# USB2_Replication.net
KiCad netlist of a schematic drawn in Altium Designer
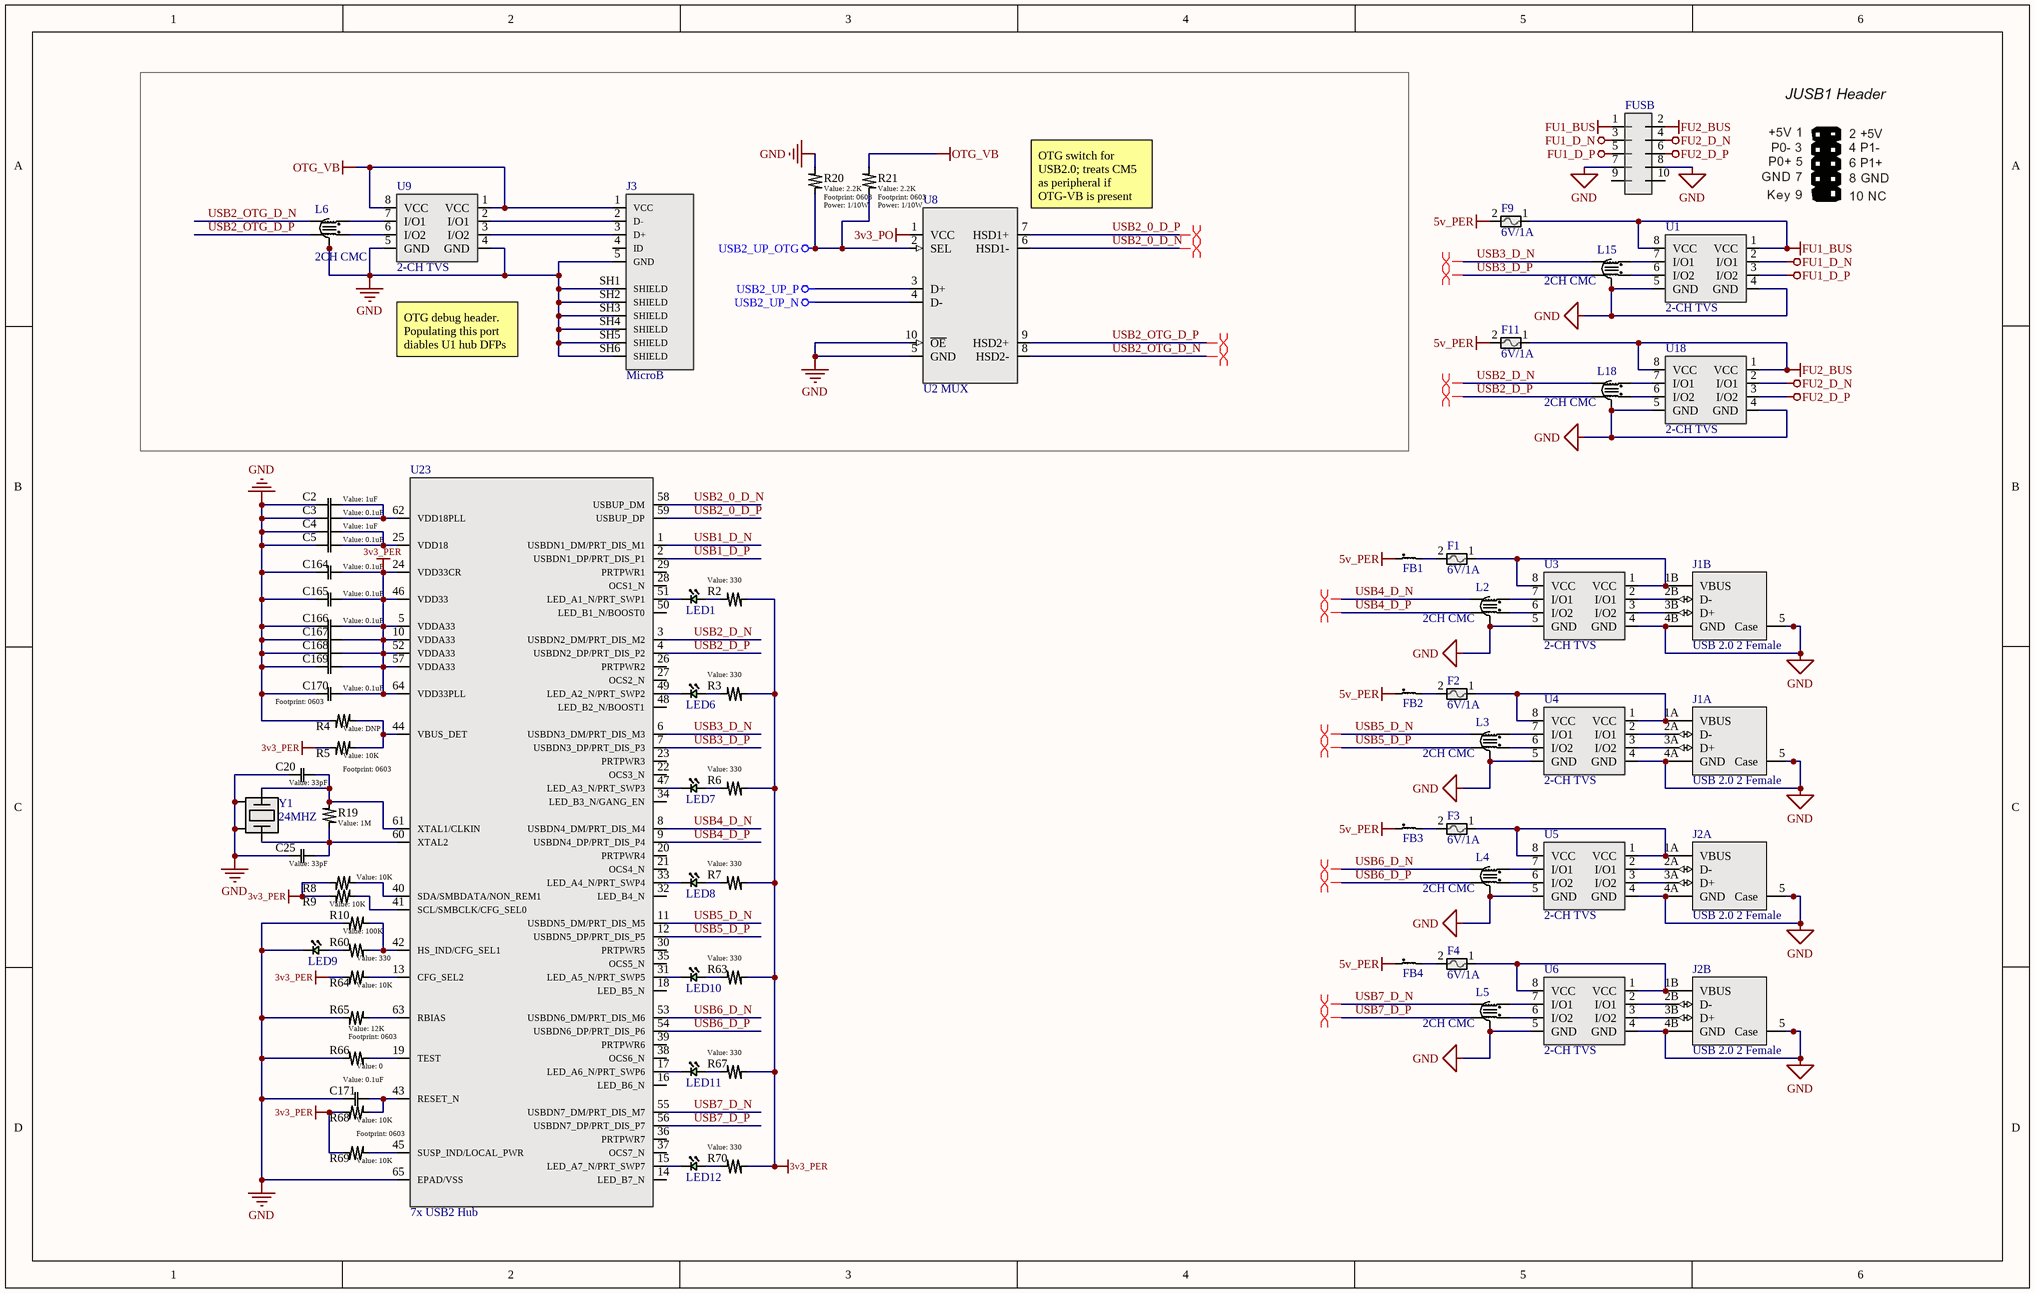
[diagram p0: USB2_Replication.SchDoc]

(export (version "E")
  (design (tool "Eeschema 10.0.6"))
  (components
    (comp (ref "C2")
      (value "1uF")
      (footprint "0603")
      (fields
        (field (name "VOLTAGE") "10V")
        (field (name "TOLERANCE") "10%")
        (field (name "Comment") "Generic Capacitor")
      )
      (libsource (lib "Capacitors") (part "Generic Capacitor"))
    )
    (comp (ref "C3")
      (value "0.1uF")
      (footprint "0603")
      (fields
        (field (name "VOLTAGE") "10V")
        (field (name "TOLERANCE") "10%")
        (field (name "Comment") "Generic Capacitor")
      )
      (libsource (lib "Capacitors") (part "Generic Capacitor"))
    )
    (comp (ref "C4")
      (value "1uF")
      (footprint "0603")
      (fields
        (field (name "VOLTAGE") "10V")
        (field (name "TOLERANCE") "10%")
        (field (name "Comment") "Generic Capacitor")
      )
      (libsource (lib "Capacitors") (part "Generic Capacitor"))
    )
    (comp (ref "C5")
      (value "0.1uF")
      (footprint "0603")
      (fields
        (field (name "VOLTAGE") "10V")
        (field (name "TOLERANCE") "10%")
        (field (name "Comment") "Generic Capacitor")
      )
      (libsource (lib "Capacitors") (part "Generic Capacitor"))
    )
    (comp (ref "C20")
      (value "33pF")
      (footprint "0603")
      (fields
        (field (name "VOLTAGE") "10V")
        (field (name "TOLERANCE") "10%")
        (field (name "Comment") "Generic Capacitor")
      )
      (libsource (lib "Capacitors") (part "Generic Capacitor"))
    )
    (comp (ref "C25")
      (value "33pF")
      (footprint "0603")
      (fields
        (field (name "VOLTAGE") "10V")
        (field (name "TOLERANCE") "10%")
        (field (name "Comment") "Generic Capacitor")
      )
      (libsource (lib "Capacitors") (part "Generic Capacitor"))
    )
    (comp (ref "C164")
      (value "0.1uF")
      (footprint "0603")
      (fields
        (field (name "VOLTAGE") "10V")
        (field (name "TOLERANCE") "10%")
        (field (name "Comment") "Generic Capacitor")
      )
      (libsource (lib "Capacitors") (part "Generic Capacitor"))
    )
    (comp (ref "C165")
      (value "0.1uF")
      (footprint "0603")
      (fields
        (field (name "VOLTAGE") "10V")
        (field (name "TOLERANCE") "10%")
        (field (name "Comment") "Generic Capacitor")
      )
      (libsource (lib "Capacitors") (part "Generic Capacitor"))
    )
    (comp (ref "C166")
      (value "0.1uF")
      (footprint "0603")
      (fields
        (field (name "VOLTAGE") "10V")
        (field (name "TOLERANCE") "10%")
        (field (name "Comment") "Generic Capacitor")
      )
      (libsource (lib "Capacitors") (part "Generic Capacitor"))
    )
    (comp (ref "C167")
      (value "Generic Capacitor")
      (footprint "0603")
      (fields (field (name "VOLTAGE") "10V") (field (name "TOLERANCE") "10%"))
      (libsource (lib "Capacitors") (part "Generic Capacitor"))
    )
    (comp (ref "C168")
      (value "Generic Capacitor")
      (footprint "0603")
      (fields (field (name "VOLTAGE") "10V") (field (name "TOLERANCE") "10%"))
      (libsource (lib "Capacitors") (part "Generic Capacitor"))
    )
    (comp (ref "C169")
      (value "Generic Capacitor")
      (footprint "0603")
      (fields (field (name "VOLTAGE") "10V") (field (name "TOLERANCE") "10%"))
      (libsource (lib "Capacitors") (part "Generic Capacitor"))
    )
    (comp (ref "C170")
      (value "0.1uF")
      (footprint "0603")
      (fields
        (field (name "VOLTAGE") "10V")
        (field (name "TOLERANCE") "10%")
        (field (name "Comment") "Generic Capacitor")
      )
      (libsource (lib "Capacitors") (part "Generic Capacitor"))
    )
    (comp (ref "C171")
      (value "0.1uF")
      (footprint "0603")
      (fields
        (field (name "VOLTAGE") "10V")
        (field (name "TOLERANCE") "10%")
        (field (name "Comment") "Generic Capacitor")
      )
      (libsource (lib "Capacitors") (part "Generic Capacitor"))
    )
    (comp (ref "F1")
      (value "6V/1A")
      (footprint "0805")
      (description "Polymeric PTC Resettable Fuse 6V 1 A Ih Surface Mount 0805 (2012 Metric), Concave")
      (fields (field (name "MANUFACTURER") "Bel") (field (name "MANUFACTURER PART NUMBER") "0ZCK0100FF2E"))
      (libsource (lib "Regulators") (part "0ZCK0100FF2E"))
    )
    (comp (ref "F2")
      (value "6V/1A")
      (footprint "0805")
      (description "Polymeric PTC Resettable Fuse 6V 1 A Ih Surface Mount 0805 (2012 Metric), Concave")
      (fields (field (name "MANUFACTURER") "Bel") (field (name "MANUFACTURER PART NUMBER") "0ZCK0100FF2E"))
      (libsource (lib "Regulators") (part "0ZCK0100FF2E"))
    )
    (comp (ref "F3")
      (value "6V/1A")
      (footprint "0805")
      (description "Polymeric PTC Resettable Fuse 6V 1 A Ih Surface Mount 0805 (2012 Metric), Concave")
      (fields (field (name "MANUFACTURER") "Bel") (field (name "MANUFACTURER PART NUMBER") "0ZCK0100FF2E"))
      (libsource (lib "Regulators") (part "0ZCK0100FF2E"))
    )
    (comp (ref "F4")
      (value "6V/1A")
      (footprint "0805")
      (description "Polymeric PTC Resettable Fuse 6V 1 A Ih Surface Mount 0805 (2012 Metric), Concave")
      (fields (field (name "MANUFACTURER") "Bel") (field (name "MANUFACTURER PART NUMBER") "0ZCK0100FF2E"))
      (libsource (lib "Regulators") (part "0ZCK0100FF2E"))
    )
    (comp (ref "F9")
      (value "6V/1A")
      (footprint "0805")
      (description "Polymeric PTC Resettable Fuse 6V 1 A Ih Surface Mount 0805 (2012 Metric), Concave")
      (fields (field (name "MANUFACTURER") "Bel") (field (name "MANUFACTURER PART NUMBER") "0ZCK0100FF2E"))
      (libsource (lib "Regulators") (part "0ZCK0100FF2E"))
    )
    (comp (ref "F11")
      (value "6V/1A")
      (footprint "0805")
      (description "Polymeric PTC Resettable Fuse 6V 1 A Ih Surface Mount 0805 (2012 Metric), Concave")
      (fields (field (name "MANUFACTURER") "Bel") (field (name "MANUFACTURER PART NUMBER") "0ZCK0100FF2E"))
      (libsource (lib "Regulators") (part "0ZCK0100FF2E"))
    )
    (comp (ref "FB1")
      (value "0603 Ferrite")
      (footprint "0603")
      (description "120 Ohms @ 100 MHz 1 Signal Line Ferrite Bead 0603 (1608 Metric) 500mA 180mOhm")
      (fields
        (field (name "MANUFACTURER") "Pulse")
        (field (name "MANUFACTURER PART NUMBER") "PE-0603FB121ST")
      )
      (libsource (lib "Inductors") (part "PE-0603FB121ST"))
    )
    (comp (ref "FB2")
      (value "0603 Ferrite")
      (footprint "0603")
      (description "120 Ohms @ 100 MHz 1 Signal Line Ferrite Bead 0603 (1608 Metric) 500mA 180mOhm")
      (fields
        (field (name "MANUFACTURER") "Pulse")
        (field (name "MANUFACTURER PART NUMBER") "PE-0603FB121ST")
      )
      (libsource (lib "Inductors") (part "PE-0603FB121ST"))
    )
    (comp (ref "FB3")
      (value "0603 Ferrite")
      (footprint "0603")
      (description "120 Ohms @ 100 MHz 1 Signal Line Ferrite Bead 0603 (1608 Metric) 500mA 180mOhm")
      (fields
        (field (name "MANUFACTURER") "Pulse")
        (field (name "MANUFACTURER PART NUMBER") "PE-0603FB121ST")
      )
      (libsource (lib "Inductors") (part "PE-0603FB121ST"))
    )
    (comp (ref "FB4")
      (value "0603 Ferrite")
      (footprint "0603")
      (description "120 Ohms @ 100 MHz 1 Signal Line Ferrite Bead 0603 (1608 Metric) 500mA 180mOhm")
      (fields
        (field (name "MANUFACTURER") "Pulse")
        (field (name "MANUFACTURER PART NUMBER") "PE-0603FB121ST")
      )
      (libsource (lib "Inductors") (part "PE-0603FB121ST"))
    )
    (comp (ref "FUSB")
      (value "10pinMobo")
      (footprint "10pinMobo")
      (description "10pin motherboard jack")
      (libsource (lib "Connectors") (part "10pinMobo"))
    )
    (comp (ref "J1")
      (value "USB 2.0 2 Female")
      (footprint "907-111A1022D10200")
      (description "USB 2.0 2 8 Female Type-A Plugin USB Connectors ROHS")
      (libsource (lib "Connectors") (part "907-111A1022D10200"))
    )
    (comp (ref "J2")
      (value "USB 2.0 2 Female")
      (footprint "907-111A1022D10200")
      (description "USB 2.0 2 8 Female Type-A Plugin USB Connectors ROHS")
      (libsource (lib "Connectors") (part "907-111A1022D10200"))
    )
    (comp (ref "J3")
      (value "MicroB")
      (footprint "10118194-0001LF")
      (description "Micro USB, Input Output Connectors, B TYPE RECEPTACLE with flange")
      (fields (field (name "MF") "Amphenol ICC") (field (name "MP") "10118194-0001LF"))
      (libsource (lib "Connectors") (part "10118194-0001LF"))
    )
    (comp (ref "L2")
      (value "2CH CMC")
      (footprint "SMD-6-2CH")
      (description "35Ω@100MHz -40℃~+85℃ 4Ω 5V 2 100mA SMD Common Mode Filters ROHS")
      (libsource (lib "Inductors") (part "ICMEF112P350MFR"))
    )
    (comp (ref "L3")
      (value "2CH CMC")
      (footprint "SMD-6-2CH")
      (description "35Ω@100MHz -40℃~+85℃ 4Ω 5V 2 100mA SMD Common Mode Filters ROHS")
      (libsource (lib "Inductors") (part "ICMEF112P350MFR"))
    )
    (comp (ref "L4")
      (value "2CH CMC")
      (footprint "SMD-6-2CH")
      (description "35Ω@100MHz -40℃~+85℃ 4Ω 5V 2 100mA SMD Common Mode Filters ROHS")
      (libsource (lib "Inductors") (part "ICMEF112P350MFR"))
    )
    (comp (ref "L5")
      (value "2CH CMC")
      (footprint "SMD-6-2CH")
      (description "35Ω@100MHz -40℃~+85℃ 4Ω 5V 2 100mA SMD Common Mode Filters ROHS")
      (libsource (lib "Inductors") (part "ICMEF112P350MFR"))
    )
    (comp (ref "L6")
      (value "2CH CMC")
      (footprint "SMD-6-2CH")
      (description "35Ω@100MHz -40℃~+85℃ 4Ω 5V 2 100mA SMD Common Mode Filters ROHS")
      (libsource (lib "Inductors") (part "ICMEF112P350MFR"))
    )
    (comp (ref "L15")
      (value "2CH CMC")
      (footprint "SMD-6-2CH")
      (description "35Ω@100MHz -40℃~+85℃ 4Ω 5V 2 100mA SMD Common Mode Filters ROHS")
      (libsource (lib "Inductors") (part "ICMEF112P350MFR"))
    )
    (comp (ref "L18")
      (value "2CH CMC")
      (footprint "SMD-6-2CH")
      (description "35Ω@100MHz -40℃~+85℃ 4Ω 5V 2 100mA SMD Common Mode Filters ROHS")
      (libsource (lib "Inductors") (part "ICMEF112P350MFR"))
    )
    (comp (ref "LED1")
      (value "LTST-C191KGKT")
      (footprint "0603 (1608 Metric) Concave")
      (description "LED Uni-Color Green 574nm 2-Pin Chip LED T/R")
      (libsource (lib "Gamber - Johnson LLC") (part "LTST-C191KGKT"))
    )
    (comp (ref "LED6")
      (value "LTST-C191KGKT")
      (footprint "0603 (1608 Metric) Concave")
      (description "LED Uni-Color Green 574nm 2-Pin Chip LED T/R")
      (libsource (lib "Gamber - Johnson LLC") (part "LTST-C191KGKT"))
    )
    (comp (ref "LED7")
      (value "LTST-C191KGKT")
      (footprint "0603 (1608 Metric) Concave")
      (description "LED Uni-Color Green 574nm 2-Pin Chip LED T/R")
      (libsource (lib "Gamber - Johnson LLC") (part "LTST-C191KGKT"))
    )
    (comp (ref "LED8")
      (value "LTST-C191KGKT")
      (footprint "0603 (1608 Metric) Concave")
      (description "LED Uni-Color Green 574nm 2-Pin Chip LED T/R")
      (libsource (lib "Gamber - Johnson LLC") (part "LTST-C191KGKT"))
    )
    (comp (ref "LED9")
      (value "LTST-C191KGKT")
      (footprint "0603 (1608 Metric) Concave")
      (description "LED Uni-Color Green 574nm 2-Pin Chip LED T/R")
      (libsource (lib "Gamber - Johnson LLC") (part "LTST-C191KGKT"))
    )
    (comp (ref "LED10")
      (value "LTST-C191KGKT")
      (footprint "0603 (1608 Metric) Concave")
      (description "LED Uni-Color Green 574nm 2-Pin Chip LED T/R")
      (libsource (lib "Gamber - Johnson LLC") (part "LTST-C191KGKT"))
    )
    (comp (ref "LED11")
      (value "LTST-C191KGKT")
      (footprint "0603 (1608 Metric) Concave")
      (description "LED Uni-Color Green 574nm 2-Pin Chip LED T/R")
      (libsource (lib "Gamber - Johnson LLC") (part "LTST-C191KGKT"))
    )
    (comp (ref "LED12")
      (value "LTST-C191KGKT")
      (footprint "0603 (1608 Metric) Concave")
      (description "LED Uni-Color Green 574nm 2-Pin Chip LED T/R")
      (libsource (lib "Gamber - Johnson LLC") (part "LTST-C191KGKT"))
    )
    (comp (ref "R2")
      (value "330")
      (footprint "0603")
      (fields
        (field (name "TOLERANCE") "1%")
        (field (name "POWER") "1/10W")
        (field (name "Comment") "Generic Resistor")
      )
      (libsource (lib "Resistors") (part "Generic Resistor"))
    )
    (comp (ref "R3")
      (value "330")
      (footprint "0603")
      (fields
        (field (name "TOLERANCE") "1%")
        (field (name "POWER") "1/10W")
        (field (name "Comment") "Generic Resistor")
      )
      (libsource (lib "Resistors") (part "Generic Resistor"))
    )
    (comp (ref "R4")
      (value "DNP")
      (footprint "0603")
      (fields
        (field (name "TOLERANCE") "1%")
        (field (name "POWER") "1/10W")
        (field (name "Comment") "Generic Resistor")
      )
      (libsource (lib "Resistors") (part "Generic Resistor"))
    )
    (comp (ref "R5")
      (value "10K")
      (footprint "0603")
      (fields
        (field (name "TOLERANCE") "1%")
        (field (name "POWER") "1/10W")
        (field (name "Comment") "Generic Resistor")
      )
      (libsource (lib "Resistors") (part "Generic Resistor"))
    )
    (comp (ref "R6")
      (value "330")
      (footprint "0603")
      (fields
        (field (name "TOLERANCE") "1%")
        (field (name "POWER") "1/10W")
        (field (name "Comment") "Generic Resistor")
      )
      (libsource (lib "Resistors") (part "Generic Resistor"))
    )
    (comp (ref "R7")
      (value "330")
      (footprint "0603")
      (fields
        (field (name "TOLERANCE") "1%")
        (field (name "POWER") "1/10W")
        (field (name "Comment") "Generic Resistor")
      )
      (libsource (lib "Resistors") (part "Generic Resistor"))
    )
    (comp (ref "R8")
      (value "10K")
      (footprint "0603")
      (fields
        (field (name "TOLERANCE") "1%")
        (field (name "POWER") "1/10W")
        (field (name "Comment") "Generic Resistor")
      )
      (libsource (lib "Resistors") (part "Generic Resistor"))
    )
    (comp (ref "R9")
      (value "10K")
      (footprint "0603")
      (fields
        (field (name "TOLERANCE") "1%")
        (field (name "POWER") "1/10W")
        (field (name "Comment") "Generic Resistor")
      )
      (libsource (lib "Resistors") (part "Generic Resistor"))
    )
    (comp (ref "R10")
      (value "100K")
      (footprint "0603")
      (fields
        (field (name "TOLERANCE") "1%")
        (field (name "POWER") "1/10W")
        (field (name "Comment") "Generic Resistor")
      )
      (libsource (lib "Resistors") (part "Generic Resistor"))
    )
    (comp (ref "R19")
      (value "1M")
      (footprint "0603")
      (fields
        (field (name "TOLERANCE") "1%")
        (field (name "POWER") "1/10W")
        (field (name "Comment") "Generic Resistor")
      )
      (libsource (lib "Resistors") (part "Generic Resistor"))
    )
    (comp (ref "R20")
      (value "2.2K")
      (footprint "0603")
      (fields
        (field (name "TOLERANCE") "1%")
        (field (name "POWER") "1/10W")
        (field (name "Comment") "Generic Resistor")
      )
      (libsource (lib "Resistors") (part "Generic Resistor"))
    )
    (comp (ref "R21")
      (value "2.2K")
      (footprint "0603")
      (fields
        (field (name "TOLERANCE") "1%")
        (field (name "POWER") "1/10W")
        (field (name "Comment") "Generic Resistor")
      )
      (libsource (lib "Resistors") (part "Generic Resistor"))
    )
    (comp (ref "R60")
      (value "330")
      (footprint "0603")
      (fields
        (field (name "TOLERANCE") "1%")
        (field (name "POWER") "1/10W")
        (field (name "Comment") "Generic Resistor")
      )
      (libsource (lib "Resistors") (part "Generic Resistor"))
    )
    (comp (ref "R63")
      (value "330")
      (footprint "0603")
      (fields
        (field (name "TOLERANCE") "1%")
        (field (name "POWER") "1/10W")
        (field (name "Comment") "Generic Resistor")
      )
      (libsource (lib "Resistors") (part "Generic Resistor"))
    )
    (comp (ref "R64")
      (value "10K")
      (footprint "0603")
      (fields
        (field (name "TOLERANCE") "1%")
        (field (name "POWER") "1/10W")
        (field (name "Comment") "Generic Resistor")
      )
      (libsource (lib "Resistors") (part "Generic Resistor"))
    )
    (comp (ref "R65")
      (value "12K")
      (footprint "0603")
      (fields
        (field (name "TOLERANCE") "1%")
        (field (name "POWER") "1/10W")
        (field (name "Comment") "Generic Resistor")
      )
      (libsource (lib "Resistors") (part "Generic Resistor"))
    )
    (comp (ref "R66")
      (value "0")
      (footprint "0603")
      (fields
        (field (name "TOLERANCE") "1%")
        (field (name "POWER") "1/10W")
        (field (name "Comment") "Generic Resistor")
      )
      (libsource (lib "Resistors") (part "Generic Resistor"))
    )
    (comp (ref "R67")
      (value "330")
      (footprint "0603")
      (fields
        (field (name "TOLERANCE") "1%")
        (field (name "POWER") "1/10W")
        (field (name "Comment") "Generic Resistor")
      )
      (libsource (lib "Resistors") (part "Generic Resistor"))
    )
    (comp (ref "R68")
      (value "10K")
      (footprint "0603")
      (fields
        (field (name "TOLERANCE") "1%")
        (field (name "POWER") "1/10W")
        (field (name "Comment") "Generic Resistor")
      )
      (libsource (lib "Resistors") (part "Generic Resistor"))
    )
    (comp (ref "R69")
      (value "10K")
      (footprint "0603")
      (fields
        (field (name "TOLERANCE") "1%")
        (field (name "POWER") "1/10W")
        (field (name "Comment") "Generic Resistor")
      )
      (libsource (lib "Resistors") (part "Generic Resistor"))
    )
    (comp (ref "R70")
      (value "330")
      (footprint "0603")
      (fields
        (field (name "TOLERANCE") "1%")
        (field (name "POWER") "1/10W")
        (field (name "Comment") "Generic Resistor")
      )
      (libsource (lib "Resistors") (part "Generic Resistor"))
    )
    (comp (ref "U1")
      (value "2-CH TVS")
      (footprint "8-SOIC")
      (description "TVS DIODE 5.25VWM 8-SOIC")
      (libsource (lib "Diodes") (part "USB6B1RL"))
    )
    (comp (ref "U3")
      (value "2-CH TVS")
      (footprint "8-SOIC")
      (description "TVS DIODE 5.25VWM 8-SOIC")
      (libsource (lib "Diodes") (part "USB6B1RL"))
    )
    (comp (ref "U4")
      (value "2-CH TVS")
      (footprint "8-SOIC")
      (description "TVS DIODE 5.25VWM 8-SOIC")
      (libsource (lib "Diodes") (part "USB6B1RL"))
    )
    (comp (ref "U5")
      (value "2-CH TVS")
      (footprint "8-SOIC")
      (description "TVS DIODE 5.25VWM 8-SOIC")
      (libsource (lib "Diodes") (part "USB6B1RL"))
    )
    (comp (ref "U6")
      (value "2-CH TVS")
      (footprint "8-SOIC")
      (description "TVS DIODE 5.25VWM 8-SOIC")
      (libsource (lib "Diodes") (part "USB6B1RL"))
    )
    (comp (ref "U8")
      (value "U2 MUX")
      (footprint "MSOP-10")
      (description "FSUSB42 Series DPDT 4.3 V 480 Mbps SMT Hi Speed USB 2.0 Switch - MSOP-10")
      (fields (field (name "MF") "ON Semiconductor") (field (name "MP") "FSUSB42MUX"))
      (libsource (lib "Misc ICs") (part "FSUSB42MUX"))
    )
    (comp (ref "U9")
      (value "2-CH TVS")
      (footprint "8-SOIC")
      (description "TVS DIODE 5.25VWM 8-SOIC")
      (libsource (lib "Diodes") (part "USB6B1RL"))
    )
    (comp (ref "U18")
      (value "2-CH TVS")
      (footprint "8-SOIC")
      (description "TVS DIODE 5.25VWM 8-SOIC")
      (libsource (lib "Diodes") (part "USB6B1RL"))
    )
    (comp (ref "U23")
      (value "7x USB2 Hub")
      (footprint "QFN-64")
      (description "USB Hub Controller USB 2.0 USB Interface 64-QFN (9x9)")
      (libsource (lib "Hub ICs") (part "USB2517-JZX"))
    )
    (comp (ref "Y1")
      (value "24MHZ")
      (footprint "SMD2520-4P")
      (description "24MHz 20pF ±10ppm ±30ppm SMD-2520-4P Crystals ROHS")
      (libsource (lib "Clock ICs") (part "CM4024M00020001"))
    )
  )
  (nets
    (net (code "1") (name "/USB1_D_N") (class "Default")
      (node (ref "U23") (pin "1") (pinfunction "USBDN1_DM/PRT_DIS_M1_1") (pintype "bidirectional"))
    )
    (net (code "2") (name "/USB1_D_P") (class "Default")
      (node (ref "U23") (pin "2") (pinfunction "USBDN1_DP/PRT_DIS_P1_2") (pintype "bidirectional"))
    )
    (net (code "3") (name "/USB2_0_D_N") (class "Default")
      (node (ref "U23") (pin "58") (pinfunction "USBUP_DM_58") (pintype "bidirectional"))
      (node (ref "U8") (pin "6") (pinfunction "HSD1-_6") (pintype "bidirectional"))
    )
    (net (code "4") (name "/USB2_0_D_P") (class "Default")
      (node (ref "U23") (pin "59") (pinfunction "USBUP_DP_59") (pintype "bidirectional"))
      (node (ref "U8") (pin "7") (pinfunction "HSD1+_7") (pintype "bidirectional"))
    )
    (net (code "5") (name "/USB2_D_N") (class "Default")
      (node (ref "L18") (pin "4") (pinfunction "4_4") (pintype "passive"))
      (node (ref "U23") (pin "3") (pinfunction "USBDN2_DM/PRT_DIS_M2_3") (pintype "bidirectional"))
    )
    (net (code "6") (name "/USB2_D_P") (class "Default")
      (node (ref "L18") (pin "3") (pinfunction "3_3") (pintype "passive"))
      (node (ref "U23") (pin "4") (pinfunction "USBDN2_DP/PRT_DIS_P2_4") (pintype "bidirectional"))
    )
    (net (code "7") (name "/USB2_OTG_D_N") (class "Default")
      (node (ref "L6") (pin "4") (pinfunction "4_4") (pintype "passive"))
      (node (ref "U8") (pin "8") (pinfunction "HSD2-_8") (pintype "bidirectional"))
    )
    (net (code "8") (name "/USB2_OTG_D_P") (class "Default")
      (node (ref "L6") (pin "3") (pinfunction "3_3") (pintype "passive"))
      (node (ref "U8") (pin "9") (pinfunction "HSD2+_9") (pintype "bidirectional"))
    )
    (net (code "9") (name "/USB3_D_N") (class "Default")
      (node (ref "L15") (pin "4") (pinfunction "4_4") (pintype "passive"))
      (node (ref "U23") (pin "6") (pinfunction "USBDN3_DM/PRT_DIS_M3_6") (pintype "bidirectional"))
    )
    (net (code "10") (name "/USB3_D_P") (class "Default")
      (node (ref "L15") (pin "3") (pinfunction "3_3") (pintype "passive"))
      (node (ref "U23") (pin "7") (pinfunction "USBDN3_DP/PRT_DIS_P3_7") (pintype "bidirectional"))
    )
    (net (code "11") (name "/USB4_D_N") (class "Default")
      (node (ref "L2") (pin "4") (pinfunction "4_4") (pintype "passive"))
      (node (ref "U23") (pin "8") (pinfunction "USBDN4_DM/PRT_DIS_M4_8") (pintype "bidirectional"))
    )
    (net (code "12") (name "/USB4_D_P") (class "Default")
      (node (ref "L2") (pin "3") (pinfunction "3_3") (pintype "passive"))
      (node (ref "U23") (pin "9") (pinfunction "USBDN4_DP/PRT_DIS_P4_9") (pintype "bidirectional"))
    )
    (net (code "13") (name "/USB5_D_N") (class "Default")
      (node (ref "L3") (pin "4") (pinfunction "4_4") (pintype "passive"))
      (node (ref "U23") (pin "11") (pinfunction "USBDN5_DM/PRT_DIS_M5_11") (pintype "bidirectional"))
    )
    (net (code "14") (name "/USB5_D_P") (class "Default")
      (node (ref "L3") (pin "3") (pinfunction "3_3") (pintype "passive"))
      (node (ref "U23") (pin "12") (pinfunction "USBDN5_DP/PRT_DIS_P5_12") (pintype "bidirectional"))
    )
    (net (code "15") (name "/USB6_D_N") (class "Default")
      (node (ref "L4") (pin "4") (pinfunction "4_4") (pintype "passive"))
      (node (ref "U23") (pin "53") (pinfunction "USBDN6_DM/PRT_DIS_M6_53") (pintype "bidirectional"))
    )
    (net (code "16") (name "/USB6_D_P") (class "Default")
      (node (ref "L4") (pin "3") (pinfunction "3_3") (pintype "passive"))
      (node (ref "U23") (pin "54") (pinfunction "USBDN6_DP/PRT_DIS_P6_54") (pintype "bidirectional"))
    )
    (net (code "17") (name "/USB7_D_N") (class "Default")
      (node (ref "L5") (pin "4") (pinfunction "4_4") (pintype "passive"))
      (node (ref "U23") (pin "55") (pinfunction "USBDN7_DM/PRT_DIS_M7_55") (pintype "bidirectional"))
    )
    (net (code "18") (name "/USB7_D_P") (class "Default")
      (node (ref "L5") (pin "3") (pinfunction "3_3") (pintype "passive"))
      (node (ref "U23") (pin "56") (pinfunction "USBDN7_DP/PRT_DIS_P7_56") (pintype "bidirectional"))
    )
    (net (code "19") (name "3v3_PER") (class "Default")
      (node (ref "C164") (pin "1") (pinfunction "1_1") (pintype "passive"))
      (node (ref "C165") (pin "1") (pinfunction "1_1") (pintype "passive"))
      (node (ref "C166") (pin "1") (pinfunction "1_1") (pintype "passive"))
      (node (ref "C167") (pin "1") (pinfunction "1_1") (pintype "passive"))
      (node (ref "C168") (pin "1") (pinfunction "1_1") (pintype "passive"))
      (node (ref "C169") (pin "1") (pinfunction "1_1") (pintype "passive"))
      (node (ref "C170") (pin "1") (pinfunction "1_1") (pintype "passive"))
      (node (ref "R2") (pin "2") (pinfunction "2_2") (pintype "passive"))
      (node (ref "R3") (pin "2") (pinfunction "2_2") (pintype "passive"))
      (node (ref "R5") (pin "1") (pinfunction "1_1") (pintype "passive"))
      (node (ref "R6") (pin "2") (pinfunction "2_2") (pintype "passive"))
      (node (ref "R63") (pin "2") (pinfunction "2_2") (pintype "passive"))
      (node (ref "R64") (pin "1") (pinfunction "1_1") (pintype "passive"))
      (node (ref "R67") (pin "2") (pinfunction "2_2") (pintype "passive"))
      (node (ref "R68") (pin "1") (pinfunction "1_1") (pintype "passive"))
      (node (ref "R69") (pin "1") (pinfunction "1_1") (pintype "passive"))
      (node (ref "R7") (pin "2") (pinfunction "2_2") (pintype "passive"))
      (node (ref "R70") (pin "2") (pinfunction "2_2") (pintype "passive"))
      (node (ref "R8") (pin "1") (pinfunction "1_1") (pintype "passive"))
      (node (ref "R9") (pin "1") (pinfunction "1_1") (pintype "passive"))
      (node (ref "U23") (pin "10") (pinfunction "VDDA33_10") (pintype "power_in"))
      (node (ref "U23") (pin "24") (pinfunction "VDD33CR_24") (pintype "power_in"))
      (node (ref "U23") (pin "46") (pinfunction "VDD33_46") (pintype "power_in"))
      (node (ref "U23") (pin "5") (pinfunction "VDDA33_5") (pintype "power_in"))
      (node (ref "U23") (pin "52") (pinfunction "VDDA33_52") (pintype "power_in"))
      (node (ref "U23") (pin "57") (pinfunction "VDDA33_57") (pintype "power_in"))
      (node (ref "U23") (pin "64") (pinfunction "VDD33PLL_64") (pintype "power_in"))
    )
    (net (code "20") (name "3v3_PO") (class "Default")
      (node (ref "U8") (pin "1") (pinfunction "VCC_1") (pintype "power_in"))
    )
    (net (code "21") (name "5v_PER") (class "Default")
      (node (ref "F11") (pin "2") (pinfunction "2_2") (pintype "passive"))
      (node (ref "F9") (pin "2") (pinfunction "2_2") (pintype "passive"))
      (node (ref "FB1") (pin "1") (pinfunction "1_1") (pintype "passive"))
      (node (ref "FB2") (pin "1") (pinfunction "1_1") (pintype "passive"))
      (node (ref "FB3") (pin "1") (pinfunction "1_1") (pintype "passive"))
      (node (ref "FB4") (pin "1") (pinfunction "1_1") (pintype "passive"))
    )
    (net (code "22") (name "FU1_BUS") (class "Default")
      (node (ref "F9") (pin "1") (pinfunction "1_1") (pintype "passive"))
      (node (ref "FUSB") (pin "1") (pinfunction "1_1") (pintype "passive"))
      (node (ref "U1") (pin "1") (pinfunction "VCC_1") (pintype "power_in"))
      (node (ref "U1") (pin "8") (pinfunction "VCC_8") (pintype "power_in"))
    )
    (net (code "23") (name "FU1_D_N") (class "Default")
      (node (ref "FUSB") (pin "3") (pinfunction "3_3") (pintype "passive"))
      (node (ref "U1") (pin "2") (pinfunction "I/O1_2") (pintype "bidirectional"))
    )
    (net (code "24") (name "FU1_D_P") (class "Default")
      (node (ref "FUSB") (pin "5") (pinfunction "5_5") (pintype "passive"))
      (node (ref "U1") (pin "3") (pinfunction "I/O2_3") (pintype "bidirectional"))
    )
    (net (code "25") (name "FU2_BUS") (class "Default")
      (node (ref "F11") (pin "1") (pinfunction "1_1") (pintype "passive"))
      (node (ref "FUSB") (pin "2") (pinfunction "2_2") (pintype "passive"))
      (node (ref "U18") (pin "1") (pinfunction "VCC_1") (pintype "power_in"))
      (node (ref "U18") (pin "8") (pinfunction "VCC_8") (pintype "power_in"))
    )
    (net (code "26") (name "FU2_D_N") (class "Default")
      (node (ref "FUSB") (pin "4") (pinfunction "4_4") (pintype "passive"))
      (node (ref "U18") (pin "2") (pinfunction "I/O1_2") (pintype "bidirectional"))
    )
    (net (code "27") (name "FU2_D_P") (class "Default")
      (node (ref "FUSB") (pin "6") (pinfunction "6_6") (pintype "passive"))
      (node (ref "U18") (pin "3") (pinfunction "I/O2_3") (pintype "bidirectional"))
    )
    (net (code "28") (name "GND") (class "Default")
      (node (ref "C164") (pin "2") (pinfunction "2_2") (pintype "passive"))
      (node (ref "C165") (pin "2") (pinfunction "2_2") (pintype "passive"))
      (node (ref "C166") (pin "2") (pinfunction "2_2") (pintype "passive"))
      (node (ref "C167") (pin "2") (pinfunction "2_2") (pintype "passive"))
      (node (ref "C168") (pin "2") (pinfunction "2_2") (pintype "passive"))
      (node (ref "C169") (pin "2") (pinfunction "2_2") (pintype "passive"))
      (node (ref "C170") (pin "2") (pinfunction "2_2") (pintype "passive"))
      (node (ref "C171") (pin "2") (pinfunction "2_2") (pintype "passive"))
      (node (ref "C2") (pin "2") (pinfunction "2_2") (pintype "passive"))
      (node (ref "C20") (pin "2") (pinfunction "2_2") (pintype "passive"))
      (node (ref "C25") (pin "2") (pinfunction "2_2") (pintype "passive"))
      (node (ref "C3") (pin "2") (pinfunction "2_2") (pintype "passive"))
      (node (ref "C4") (pin "2") (pinfunction "2_2") (pintype "passive"))
      (node (ref "C5") (pin "2") (pinfunction "2_2") (pintype "passive"))
      (node (ref "FUSB") (pin "7") (pinfunction "7_7") (pintype "passive"))
      (node (ref "FUSB") (pin "8") (pinfunction "8_8") (pintype "passive"))
      (node (ref "J1") (pin "4A") (pinfunction "GND_4A") (pintype "power_in"))
      (node (ref "J1") (pin "4B") (pinfunction "GND_4B") (pintype "power_in"))
      (node (ref "J1") (pin "5") (pinfunction "Case_5") (pintype "passive"))
      (node (ref "J2") (pin "4A") (pinfunction "GND_4A") (pintype "power_in"))
      (node (ref "J2") (pin "4B") (pinfunction "GND_4B") (pintype "power_in"))
      (node (ref "J2") (pin "5") (pinfunction "Case_5") (pintype "passive"))
      (node (ref "J3") (pin "5") (pinfunction "GND_5") (pintype "power_in"))
      (node (ref "J3") (pin "SH1") (pinfunction "SHIELD_SH1") (pintype "passive"))
      (node (ref "J3") (pin "SH2") (pinfunction "SHIELD_SH2") (pintype "passive"))
      (node (ref "J3") (pin "SH3") (pinfunction "SHIELD_SH3") (pintype "passive"))
      (node (ref "J3") (pin "SH4") (pinfunction "SHIELD_SH4") (pintype "passive"))
      (node (ref "J3") (pin "SH5") (pinfunction "SHIELD_SH5") (pintype "passive"))
      (node (ref "J3") (pin "SH6") (pinfunction "SHIELD_SH6") (pintype "passive"))
      (node (ref "L15") (pin "5") (pinfunction "5_5") (pintype "passive"))
      (node (ref "L15") (pin "6") (pinfunction "6_6") (pintype "passive"))
      (node (ref "L18") (pin "5") (pinfunction "5_5") (pintype "passive"))
      (node (ref "L18") (pin "6") (pinfunction "6_6") (pintype "passive"))
      (node (ref "L2") (pin "5") (pinfunction "5_5") (pintype "passive"))
      (node (ref "L2") (pin "6") (pinfunction "6_6") (pintype "passive"))
      (node (ref "L3") (pin "5") (pinfunction "5_5") (pintype "passive"))
      (node (ref "L3") (pin "6") (pinfunction "6_6") (pintype "passive"))
      (node (ref "L4") (pin "5") (pinfunction "5_5") (pintype "passive"))
      (node (ref "L4") (pin "6") (pinfunction "6_6") (pintype "passive"))
      (node (ref "L5") (pin "5") (pinfunction "5_5") (pintype "passive"))
      (node (ref "L5") (pin "6") (pinfunction "6_6") (pintype "passive"))
      (node (ref "L6") (pin "5") (pinfunction "5_5") (pintype "passive"))
      (node (ref "L6") (pin "6") (pinfunction "6_6") (pintype "passive"))
      (node (ref "LED9") (pin "1") (pinfunction "Cathode_1") (pintype "passive"))
      (node (ref "R10") (pin "1") (pinfunction "1_1") (pintype "passive"))
      (node (ref "R20") (pin "1") (pinfunction "1_1") (pintype "passive"))
      (node (ref "R4") (pin "1") (pinfunction "1_1") (pintype "passive"))
      (node (ref "R65") (pin "1") (pinfunction "1_1") (pintype "passive"))
      (node (ref "R66") (pin "1") (pinfunction "1_1") (pintype "passive"))
      (node (ref "U1") (pin "4") (pinfunction "GND_4") (pintype "power_in"))
      (node (ref "U1") (pin "5") (pinfunction "GND_5") (pintype "power_in"))
      (node (ref "U18") (pin "4") (pinfunction "GND_4") (pintype "power_in"))
      (node (ref "U18") (pin "5") (pinfunction "GND_5") (pintype "power_in"))
      (node (ref "U23") (pin "65") (pinfunction "EPAD/VSS_65") (pintype "passive"))
      (node (ref "U3") (pin "4") (pinfunction "GND_4") (pintype "power_in"))
      (node (ref "U3") (pin "5") (pinfunction "GND_5") (pintype "power_in"))
      (node (ref "U4") (pin "4") (pinfunction "GND_4") (pintype "power_in"))
      (node (ref "U4") (pin "5") (pinfunction "GND_5") (pintype "power_in"))
      (node (ref "U5") (pin "4") (pinfunction "GND_4") (pintype "power_in"))
      (node (ref "U5") (pin "5") (pinfunction "GND_5") (pintype "power_in"))
      (node (ref "U6") (pin "4") (pinfunction "GND_4") (pintype "power_in"))
      (node (ref "U6") (pin "5") (pinfunction "GND_5") (pintype "power_in"))
      (node (ref "U8") (pin "10") (pinfunction "~{OE}_10") (pintype "input"))
      (node (ref "U8") (pin "5") (pinfunction "GND_5") (pintype "power_in"))
      (node (ref "U9") (pin "4") (pinfunction "GND_4") (pintype "power_in"))
      (node (ref "U9") (pin "5") (pinfunction "GND_5") (pintype "power_in"))
      (node (ref "Y1") (pin "2") (pinfunction "GND_2") (pintype "power_in"))
      (node (ref "Y1") (pin "4") (pinfunction "GND_4") (pintype "power_in"))
    )
    (net (code "29") (name "Net-(F1-Pad2)") (class "Default")
      (node (ref "F1") (pin "2") (pinfunction "2_2") (pintype "passive"))
      (node (ref "FB1") (pin "2") (pinfunction "2_2") (pintype "passive"))
    )
    (net (code "30") (name "Net-(F2-Pad2)") (class "Default")
      (node (ref "F2") (pin "2") (pinfunction "2_2") (pintype "passive"))
      (node (ref "FB2") (pin "2") (pinfunction "2_2") (pintype "passive"))
    )
    (net (code "31") (name "Net-(F3-Pad2)") (class "Default")
      (node (ref "F3") (pin "2") (pinfunction "2_2") (pintype "passive"))
      (node (ref "FB3") (pin "2") (pinfunction "2_2") (pintype "passive"))
    )
    (net (code "32") (name "Net-(F4-Pad2)") (class "Default")
      (node (ref "F4") (pin "2") (pinfunction "2_2") (pintype "passive"))
      (node (ref "FB4") (pin "2") (pinfunction "2_2") (pintype "passive"))
    )
    (net (code "33") (name "Net-(J1A-D+)") (class "Default")
      (node (ref "J1") (pin "3A") (pinfunction "D+_3A") (pintype "bidirectional"))
      (node (ref "U4") (pin "3") (pinfunction "I/O2_3") (pintype "bidirectional"))
    )
    (net (code "34") (name "Net-(J1A-D-)") (class "Default")
      (node (ref "J1") (pin "2A") (pinfunction "D-_2A") (pintype "bidirectional"))
      (node (ref "U4") (pin "2") (pinfunction "I/O1_2") (pintype "bidirectional"))
    )
    (net (code "35") (name "Net-(J1A-VBUS)") (class "Default")
      (node (ref "F2") (pin "1") (pinfunction "1_1") (pintype "passive"))
      (node (ref "J1") (pin "1A") (pinfunction "VBUS_1A") (pintype "power_in"))
      (node (ref "U4") (pin "1") (pinfunction "VCC_1") (pintype "power_in"))
      (node (ref "U4") (pin "8") (pinfunction "VCC_8") (pintype "power_in"))
    )
    (net (code "36") (name "Net-(J1B-D+)") (class "Default")
      (node (ref "J1") (pin "3B") (pinfunction "D+_3B") (pintype "bidirectional"))
      (node (ref "U3") (pin "3") (pinfunction "I/O2_3") (pintype "bidirectional"))
    )
    (net (code "37") (name "Net-(J1B-D-)") (class "Default")
      (node (ref "J1") (pin "2B") (pinfunction "D-_2B") (pintype "bidirectional"))
      (node (ref "U3") (pin "2") (pinfunction "I/O1_2") (pintype "bidirectional"))
    )
    (net (code "38") (name "Net-(J1B-VBUS)") (class "Default")
      (node (ref "F1") (pin "1") (pinfunction "1_1") (pintype "passive"))
      (node (ref "J1") (pin "1B") (pinfunction "VBUS_1B") (pintype "power_in"))
      (node (ref "U3") (pin "1") (pinfunction "VCC_1") (pintype "power_in"))
      (node (ref "U3") (pin "8") (pinfunction "VCC_8") (pintype "power_in"))
    )
    (net (code "39") (name "Net-(J2A-D+)") (class "Default")
      (node (ref "J2") (pin "3A") (pinfunction "D+_3A") (pintype "bidirectional"))
      (node (ref "U5") (pin "3") (pinfunction "I/O2_3") (pintype "bidirectional"))
    )
    (net (code "40") (name "Net-(J2A-D-)") (class "Default")
      (node (ref "J2") (pin "2A") (pinfunction "D-_2A") (pintype "bidirectional"))
      (node (ref "U5") (pin "2") (pinfunction "I/O1_2") (pintype "bidirectional"))
    )
    (net (code "41") (name "Net-(J2A-VBUS)") (class "Default")
      (node (ref "F3") (pin "1") (pinfunction "1_1") (pintype "passive"))
      (node (ref "J2") (pin "1A") (pinfunction "VBUS_1A") (pintype "power_in"))
      (node (ref "U5") (pin "1") (pinfunction "VCC_1") (pintype "power_in"))
      (node (ref "U5") (pin "8") (pinfunction "VCC_8") (pintype "power_in"))
    )
    (net (code "42") (name "Net-(J2B-D+)") (class "Default")
      (node (ref "J2") (pin "3B") (pinfunction "D+_3B") (pintype "bidirectional"))
      (node (ref "U6") (pin "3") (pinfunction "I/O2_3") (pintype "bidirectional"))
    )
    (net (code "43") (name "Net-(J2B-D-)") (class "Default")
      (node (ref "J2") (pin "2B") (pinfunction "D-_2B") (pintype "bidirectional"))
      (node (ref "U6") (pin "2") (pinfunction "I/O1_2") (pintype "bidirectional"))
    )
    (net (code "44") (name "Net-(J2B-VBUS)") (class "Default")
      (node (ref "F4") (pin "1") (pinfunction "1_1") (pintype "passive"))
      (node (ref "J2") (pin "1B") (pinfunction "VBUS_1B") (pintype "power_in"))
      (node (ref "U6") (pin "1") (pinfunction "VCC_1") (pintype "power_in"))
      (node (ref "U6") (pin "8") (pinfunction "VCC_8") (pintype "power_in"))
    )
    (net (code "45") (name "Net-(J3-D+)") (class "Default")
      (node (ref "J3") (pin "3") (pinfunction "D+_3") (pintype "bidirectional"))
      (node (ref "U9") (pin "3") (pinfunction "I/O2_3") (pintype "bidirectional"))
    )
    (net (code "46") (name "Net-(J3-D-)") (class "Default")
      (node (ref "J3") (pin "2") (pinfunction "D-_2") (pintype "bidirectional"))
      (node (ref "U9") (pin "2") (pinfunction "I/O1_2") (pintype "bidirectional"))
    )
    (net (code "47") (name "Net-(L2-Pad1)") (class "Default")
      (node (ref "L2") (pin "1") (pinfunction "1_1") (pintype "passive"))
      (node (ref "U3") (pin "7") (pinfunction "I/O1_7") (pintype "bidirectional"))
    )
    (net (code "48") (name "Net-(L2-Pad2)") (class "Default")
      (node (ref "L2") (pin "2") (pinfunction "2_2") (pintype "passive"))
      (node (ref "U3") (pin "6") (pinfunction "I/O2_6") (pintype "bidirectional"))
    )
    (net (code "49") (name "Net-(L3-Pad1)") (class "Default")
      (node (ref "L3") (pin "1") (pinfunction "1_1") (pintype "passive"))
      (node (ref "U4") (pin "7") (pinfunction "I/O1_7") (pintype "bidirectional"))
    )
    (net (code "50") (name "Net-(L3-Pad2)") (class "Default")
      (node (ref "L3") (pin "2") (pinfunction "2_2") (pintype "passive"))
      (node (ref "U4") (pin "6") (pinfunction "I/O2_6") (pintype "bidirectional"))
    )
    (net (code "51") (name "Net-(L4-Pad1)") (class "Default")
      (node (ref "L4") (pin "1") (pinfunction "1_1") (pintype "passive"))
      (node (ref "U5") (pin "7") (pinfunction "I/O1_7") (pintype "bidirectional"))
    )
    (net (code "52") (name "Net-(L4-Pad2)") (class "Default")
      (node (ref "L4") (pin "2") (pinfunction "2_2") (pintype "passive"))
      (node (ref "U5") (pin "6") (pinfunction "I/O2_6") (pintype "bidirectional"))
    )
    (net (code "53") (name "Net-(L5-Pad1)") (class "Default")
      (node (ref "L5") (pin "1") (pinfunction "1_1") (pintype "passive"))
      (node (ref "U6") (pin "7") (pinfunction "I/O1_7") (pintype "bidirectional"))
    )
    (net (code "54") (name "Net-(L5-Pad2)") (class "Default")
      (node (ref "L5") (pin "2") (pinfunction "2_2") (pintype "passive"))
      (node (ref "U6") (pin "6") (pinfunction "I/O2_6") (pintype "bidirectional"))
    )
    (net (code "55") (name "Net-(L6-Pad1)") (class "Default")
      (node (ref "L6") (pin "1") (pinfunction "1_1") (pintype "passive"))
      (node (ref "U9") (pin "7") (pinfunction "I/O1_7") (pintype "bidirectional"))
    )
    (net (code "56") (name "Net-(L6-Pad2)") (class "Default")
      (node (ref "L6") (pin "2") (pinfunction "2_2") (pintype "passive"))
      (node (ref "U9") (pin "6") (pinfunction "I/O2_6") (pintype "bidirectional"))
    )
    (net (code "57") (name "Net-(L15-Pad1)") (class "Default")
      (node (ref "L15") (pin "1") (pinfunction "1_1") (pintype "passive"))
      (node (ref "U1") (pin "7") (pinfunction "I/O1_7") (pintype "bidirectional"))
    )
    (net (code "58") (name "Net-(L15-Pad2)") (class "Default")
      (node (ref "L15") (pin "2") (pinfunction "2_2") (pintype "passive"))
      (node (ref "U1") (pin "6") (pinfunction "I/O2_6") (pintype "bidirectional"))
    )
    (net (code "59") (name "Net-(L18-Pad1)") (class "Default")
      (node (ref "L18") (pin "1") (pinfunction "1_1") (pintype "passive"))
      (node (ref "U18") (pin "7") (pinfunction "I/O1_7") (pintype "bidirectional"))
    )
    (net (code "60") (name "Net-(L18-Pad2)") (class "Default")
      (node (ref "L18") (pin "2") (pinfunction "2_2") (pintype "passive"))
      (node (ref "U18") (pin "6") (pinfunction "I/O2_6") (pintype "bidirectional"))
    )
    (net (code "61") (name "Net-(LED1-Anode)") (class "Default")
      (node (ref "LED1") (pin "2") (pinfunction "Anode_2") (pintype "passive"))
      (node (ref "R2") (pin "1") (pinfunction "1_1") (pintype "passive"))
    )
    (net (code "62") (name "Net-(LED1-Cathode)") (class "Default")
      (node (ref "LED1") (pin "1") (pinfunction "Cathode_1") (pintype "passive"))
      (node (ref "U23") (pin "51") (pinfunction "LED_A1_N/PRT_SWP1_51") (pintype "bidirectional"))
    )
    (net (code "63") (name "Net-(LED6-Anode)") (class "Default")
      (node (ref "LED6") (pin "2") (pinfunction "Anode_2") (pintype "passive"))
      (node (ref "R3") (pin "1") (pinfunction "1_1") (pintype "passive"))
    )
    (net (code "64") (name "Net-(LED6-Cathode)") (class "Default")
      (node (ref "LED6") (pin "1") (pinfunction "Cathode_1") (pintype "passive"))
      (node (ref "U23") (pin "49") (pinfunction "LED_A2_N/PRT_SWP2_49") (pintype "bidirectional"))
    )
    (net (code "65") (name "Net-(LED7-Anode)") (class "Default")
      (node (ref "LED7") (pin "2") (pinfunction "Anode_2") (pintype "passive"))
      (node (ref "R6") (pin "1") (pinfunction "1_1") (pintype "passive"))
    )
    (net (code "66") (name "Net-(LED7-Cathode)") (class "Default")
      (node (ref "LED7") (pin "1") (pinfunction "Cathode_1") (pintype "passive"))
      (node (ref "U23") (pin "47") (pinfunction "LED_A3_N/PRT_SWP3_47") (pintype "bidirectional"))
    )
    (net (code "67") (name "Net-(LED8-Anode)") (class "Default")
      (node (ref "LED8") (pin "2") (pinfunction "Anode_2") (pintype "passive"))
      (node (ref "R7") (pin "1") (pinfunction "1_1") (pintype "passive"))
    )
    (net (code "68") (name "Net-(LED8-Cathode)") (class "Default")
      (node (ref "LED8") (pin "1") (pinfunction "Cathode_1") (pintype "passive"))
      (node (ref "U23") (pin "33") (pinfunction "LED_A4_N/PRT_SWP4_33") (pintype "bidirectional"))
    )
    (net (code "69") (name "Net-(LED9-Anode)") (class "Default")
      (node (ref "LED9") (pin "2") (pinfunction "Anode_2") (pintype "passive"))
      (node (ref "R60") (pin "1") (pinfunction "1_1") (pintype "passive"))
    )
    (net (code "70") (name "Net-(LED10-Anode)") (class "Default")
      (node (ref "LED10") (pin "2") (pinfunction "Anode_2") (pintype "passive"))
      (node (ref "R63") (pin "1") (pinfunction "1_1") (pintype "passive"))
    )
    (net (code "71") (name "Net-(LED10-Cathode)") (class "Default")
      (node (ref "LED10") (pin "1") (pinfunction "Cathode_1") (pintype "passive"))
      (node (ref "U23") (pin "31") (pinfunction "LED_A5_N/PRT_SWP5_31") (pintype "bidirectional"))
    )
    (net (code "72") (name "Net-(LED11-Anode)") (class "Default")
      (node (ref "LED11") (pin "2") (pinfunction "Anode_2") (pintype "passive"))
      (node (ref "R67") (pin "1") (pinfunction "1_1") (pintype "passive"))
    )
    (net (code "73") (name "Net-(LED11-Cathode)") (class "Default")
      (node (ref "LED11") (pin "1") (pinfunction "Cathode_1") (pintype "passive"))
      (node (ref "U23") (pin "17") (pinfunction "LED_A6_N/PRT_SWP6_17") (pintype "bidirectional"))
    )
    (net (code "74") (name "Net-(LED12-Anode)") (class "Default")
      (node (ref "LED12") (pin "2") (pinfunction "Anode_2") (pintype "passive"))
      (node (ref "R70") (pin "1") (pinfunction "1_1") (pintype "passive"))
    )
    (net (code "75") (name "Net-(LED12-Cathode)") (class "Default")
      (node (ref "LED12") (pin "1") (pinfunction "Cathode_1") (pintype "passive"))
      (node (ref "U23") (pin "15") (pinfunction "LED_A7_N/PRT_SWP7_15") (pintype "bidirectional"))
    )
    (net (code "76") (name "Net-(U23-CFG_SEL2)") (class "Default")
      (node (ref "R64") (pin "2") (pinfunction "2_2") (pintype "passive"))
      (node (ref "U23") (pin "13") (pinfunction "CFG_SEL2_13") (pintype "bidirectional"))
    )
    (net (code "77") (name "Net-(U23-HS_IND{slash}CFG_SEL1)") (class "Default")
      (node (ref "R10") (pin "2") (pinfunction "2_2") (pintype "passive"))
      (node (ref "R60") (pin "2") (pinfunction "2_2") (pintype "passive"))
      (node (ref "U23") (pin "42") (pinfunction "HS_IND/CFG_SEL1_42") (pintype "bidirectional"))
    )
    (net (code "78") (name "Net-(U23-RBIAS)") (class "Default")
      (node (ref "R65") (pin "2") (pinfunction "2_2") (pintype "passive"))
      (node (ref "U23") (pin "63") (pinfunction "RBIAS_63") (pintype "bidirectional"))
    )
    (net (code "79") (name "Net-(U23-RESET_N)") (class "Default")
      (node (ref "C171") (pin "1") (pinfunction "1_1") (pintype "passive"))
      (node (ref "R68") (pin "2") (pinfunction "2_2") (pintype "passive"))
      (node (ref "U23") (pin "43") (pinfunction "RESET_N_43") (pintype "bidirectional"))
    )
    (net (code "80") (name "Net-(U23-SCL{slash}SMBCLK{slash}CFG_SEL0)") (class "Default")
      (node (ref "R9") (pin "2") (pinfunction "2_2") (pintype "passive"))
      (node (ref "U23") (pin "41") (pinfunction "SCL/SMBCLK/CFG_SEL0_41") (pintype "bidirectional"))
    )
    (net (code "81") (name "Net-(U23-SDA{slash}SMBDATA{slash}NON_REM1)") (class "Default")
      (node (ref "R8") (pin "2") (pinfunction "2_2") (pintype "passive"))
      (node (ref "U23") (pin "40") (pinfunction "SDA/SMBDATA/NON_REM1_40") (pintype "bidirectional"))
    )
    (net (code "82") (name "Net-(U23-SUSP_IND{slash}LOCAL_PWR)") (class "Default")
      (node (ref "R69") (pin "2") (pinfunction "2_2") (pintype "passive"))
      (node (ref "U23") (pin "45") (pinfunction "SUSP_IND/LOCAL_PWR_45") (pintype "bidirectional"))
    )
    (net (code "83") (name "Net-(U23-TEST)") (class "Default")
      (node (ref "R66") (pin "2") (pinfunction "2_2") (pintype "passive"))
      (node (ref "U23") (pin "19") (pinfunction "TEST_19") (pintype "bidirectional"))
    )
    (net (code "84") (name "Net-(U23-VBUS_DET)") (class "Default")
      (node (ref "R4") (pin "2") (pinfunction "2_2") (pintype "passive"))
      (node (ref "R5") (pin "2") (pinfunction "2_2") (pintype "passive"))
      (node (ref "U23") (pin "44") (pinfunction "VBUS_DET_44") (pintype "bidirectional"))
    )
    (net (code "85") (name "Net-(U23-VDD18)") (class "Default")
      (node (ref "C4") (pin "1") (pinfunction "1_1") (pintype "passive"))
      (node (ref "C5") (pin "1") (pinfunction "1_1") (pintype "passive"))
      (node (ref "U23") (pin "25") (pinfunction "VDD18_25") (pintype "power_in"))
    )
    (net (code "86") (name "Net-(U23-VDD18PLL)") (class "Default")
      (node (ref "C2") (pin "1") (pinfunction "1_1") (pintype "passive"))
      (node (ref "C3") (pin "1") (pinfunction "1_1") (pintype "passive"))
      (node (ref "U23") (pin "62") (pinfunction "VDD18PLL_62") (pintype "power_in"))
    )
    (net (code "87") (name "Net-(U23-XTAL1{slash}CLKIN)") (class "Default")
      (node (ref "C20") (pin "1") (pinfunction "1_1") (pintype "passive"))
      (node (ref "R19") (pin "1") (pinfunction "1_1") (pintype "passive"))
      (node (ref "U23") (pin "61") (pinfunction "XTAL1/CLKIN_61") (pintype "bidirectional"))
      (node (ref "Y1") (pin "1") (pintype "passive"))
    )
    (net (code "88") (name "Net-(U23-XTAL2)") (class "Default")
      (node (ref "C25") (pin "1") (pinfunction "1_1") (pintype "passive"))
      (node (ref "R19") (pin "2") (pinfunction "2_2") (pintype "passive"))
      (node (ref "U23") (pin "60") (pinfunction "XTAL2_60") (pintype "bidirectional"))
      (node (ref "Y1") (pin "3") (pintype "passive"))
    )
    (net (code "89") (name "OTG_VB") (class "Default")
      (node (ref "J3") (pin "1") (pinfunction "VCC_1") (pintype "power_in"))
      (node (ref "R21") (pin "1") (pinfunction "1_1") (pintype "passive"))
      (node (ref "U9") (pin "1") (pinfunction "VCC_1") (pintype "power_in"))
      (node (ref "U9") (pin "8") (pinfunction "VCC_8") (pintype "power_in"))
    )
    (net (code "90") (name "USB2_UP_N") (class "Default")
      (node (ref "U8") (pin "4") (pinfunction "D-_4") (pintype "bidirectional"))
    )
    (net (code "91") (name "USB2_UP_OTG") (class "Default")
      (node (ref "R20") (pin "2") (pinfunction "2_2") (pintype "passive"))
      (node (ref "R21") (pin "2") (pinfunction "2_2") (pintype "passive"))
      (node (ref "U8") (pin "2") (pinfunction "SEL_2") (pintype "input"))
    )
    (net (code "92") (name "USB2_UP_P") (class "Default")
      (node (ref "U8") (pin "3") (pinfunction "D+_3") (pintype "bidirectional"))
    )
    (net (code "93") (name "unconnected-(FUSB-Pad9)") (class "Default")
      (node (ref "FUSB") (pin "9") (pinfunction "9_9") (pintype "passive"))
    )
    (net (code "94") (name "unconnected-(FUSB-Pad10)") (class "Default")
      (node (ref "FUSB") (pin "10") (pinfunction "10_10") (pintype "passive"))
    )
    (net (code "95") (name "unconnected-(J3-ID-Pad4)") (class "Default")
      (node (ref "J3") (pin "4") (pinfunction "ID_4") (pintype "bidirectional"))
    )
    (net (code "96") (name "unconnected-(U23-LED_B1_N{slash}BOOST0-Pad50)") (class "Default")
      (node (ref "U23") (pin "50") (pinfunction "LED_B1_N/BOOST0_50") (pintype "bidirectional"))
    )
    (net (code "97") (name "unconnected-(U23-LED_B2_N{slash}BOOST1-Pad48)") (class "Default")
      (node (ref "U23") (pin "48") (pinfunction "LED_B2_N/BOOST1_48") (pintype "bidirectional"))
    )
    (net (code "98") (name "unconnected-(U23-LED_B3_N{slash}GANG_EN-Pad34)") (class "Default")
      (node (ref "U23") (pin "34") (pinfunction "LED_B3_N/GANG_EN_34") (pintype "bidirectional"))
    )
    (net (code "99") (name "unconnected-(U23-LED_B4_N-Pad32)") (class "Default")
      (node (ref "U23") (pin "32") (pinfunction "LED_B4_N_32") (pintype "bidirectional"))
    )
    (net (code "100") (name "unconnected-(U23-LED_B5_N-Pad18)") (class "Default")
      (node (ref "U23") (pin "18") (pinfunction "LED_B5_N_18") (pintype "bidirectional"))
    )
    (net (code "101") (name "unconnected-(U23-LED_B6_N-Pad16)") (class "Default")
      (node (ref "U23") (pin "16") (pinfunction "LED_B6_N_16") (pintype "bidirectional"))
    )
    (net (code "102") (name "unconnected-(U23-LED_B7_N-Pad14)") (class "Default")
      (node (ref "U23") (pin "14") (pinfunction "LED_B7_N_14") (pintype "bidirectional"))
    )
    (net (code "103") (name "unconnected-(U23-OCS1_N-Pad28)") (class "Default")
      (node (ref "U23") (pin "28") (pinfunction "OCS1_N_28") (pintype "bidirectional"))
    )
    (net (code "104") (name "unconnected-(U23-OCS2_N-Pad27)") (class "Default")
      (node (ref "U23") (pin "27") (pinfunction "OCS2_N_27") (pintype "bidirectional"))
    )
    (net (code "105") (name "unconnected-(U23-OCS3_N-Pad22)") (class "Default")
      (node (ref "U23") (pin "22") (pinfunction "OCS3_N_22") (pintype "bidirectional"))
    )
    (net (code "106") (name "unconnected-(U23-OCS4_N-Pad21)") (class "Default")
      (node (ref "U23") (pin "21") (pinfunction "OCS4_N_21") (pintype "bidirectional"))
    )
    (net (code "107") (name "unconnected-(U23-OCS5_N-Pad35)") (class "Default")
      (node (ref "U23") (pin "35") (pinfunction "OCS5_N_35") (pintype "bidirectional"))
    )
    (net (code "108") (name "unconnected-(U23-OCS6_N-Pad38)") (class "Default")
      (node (ref "U23") (pin "38") (pinfunction "OCS6_N_38") (pintype "bidirectional"))
    )
    (net (code "109") (name "unconnected-(U23-OCS7_N-Pad37)") (class "Default")
      (node (ref "U23") (pin "37") (pinfunction "OCS7_N_37") (pintype "bidirectional"))
    )
    (net (code "110") (name "unconnected-(U23-PRTPWR1-Pad29)") (class "Default")
      (node (ref "U23") (pin "29") (pinfunction "PRTPWR1_29") (pintype "bidirectional"))
    )
    (net (code "111") (name "unconnected-(U23-PRTPWR2-Pad26)") (class "Default")
      (node (ref "U23") (pin "26") (pinfunction "PRTPWR2_26") (pintype "bidirectional"))
    )
    (net (code "112") (name "unconnected-(U23-PRTPWR3-Pad23)") (class "Default")
      (node (ref "U23") (pin "23") (pinfunction "PRTPWR3_23") (pintype "bidirectional"))
    )
    (net (code "113") (name "unconnected-(U23-PRTPWR4-Pad20)") (class "Default")
      (node (ref "U23") (pin "20") (pinfunction "PRTPWR4_20") (pintype "bidirectional"))
    )
    (net (code "114") (name "unconnected-(U23-PRTPWR5-Pad30)") (class "Default")
      (node (ref "U23") (pin "30") (pinfunction "PRTPWR5_30") (pintype "bidirectional"))
    )
    (net (code "115") (name "unconnected-(U23-PRTPWR6-Pad39)") (class "Default")
      (node (ref "U23") (pin "39") (pinfunction "PRTPWR6_39") (pintype "bidirectional"))
    )
    (net (code "116") (name "unconnected-(U23-PRTPWR7-Pad36)") (class "Default")
      (node (ref "U23") (pin "36") (pinfunction "PRTPWR7_36") (pintype "bidirectional"))
    )
  )
)
